# Sheamtic.net
KiCad netlist of a schematic drawn in EAGLE
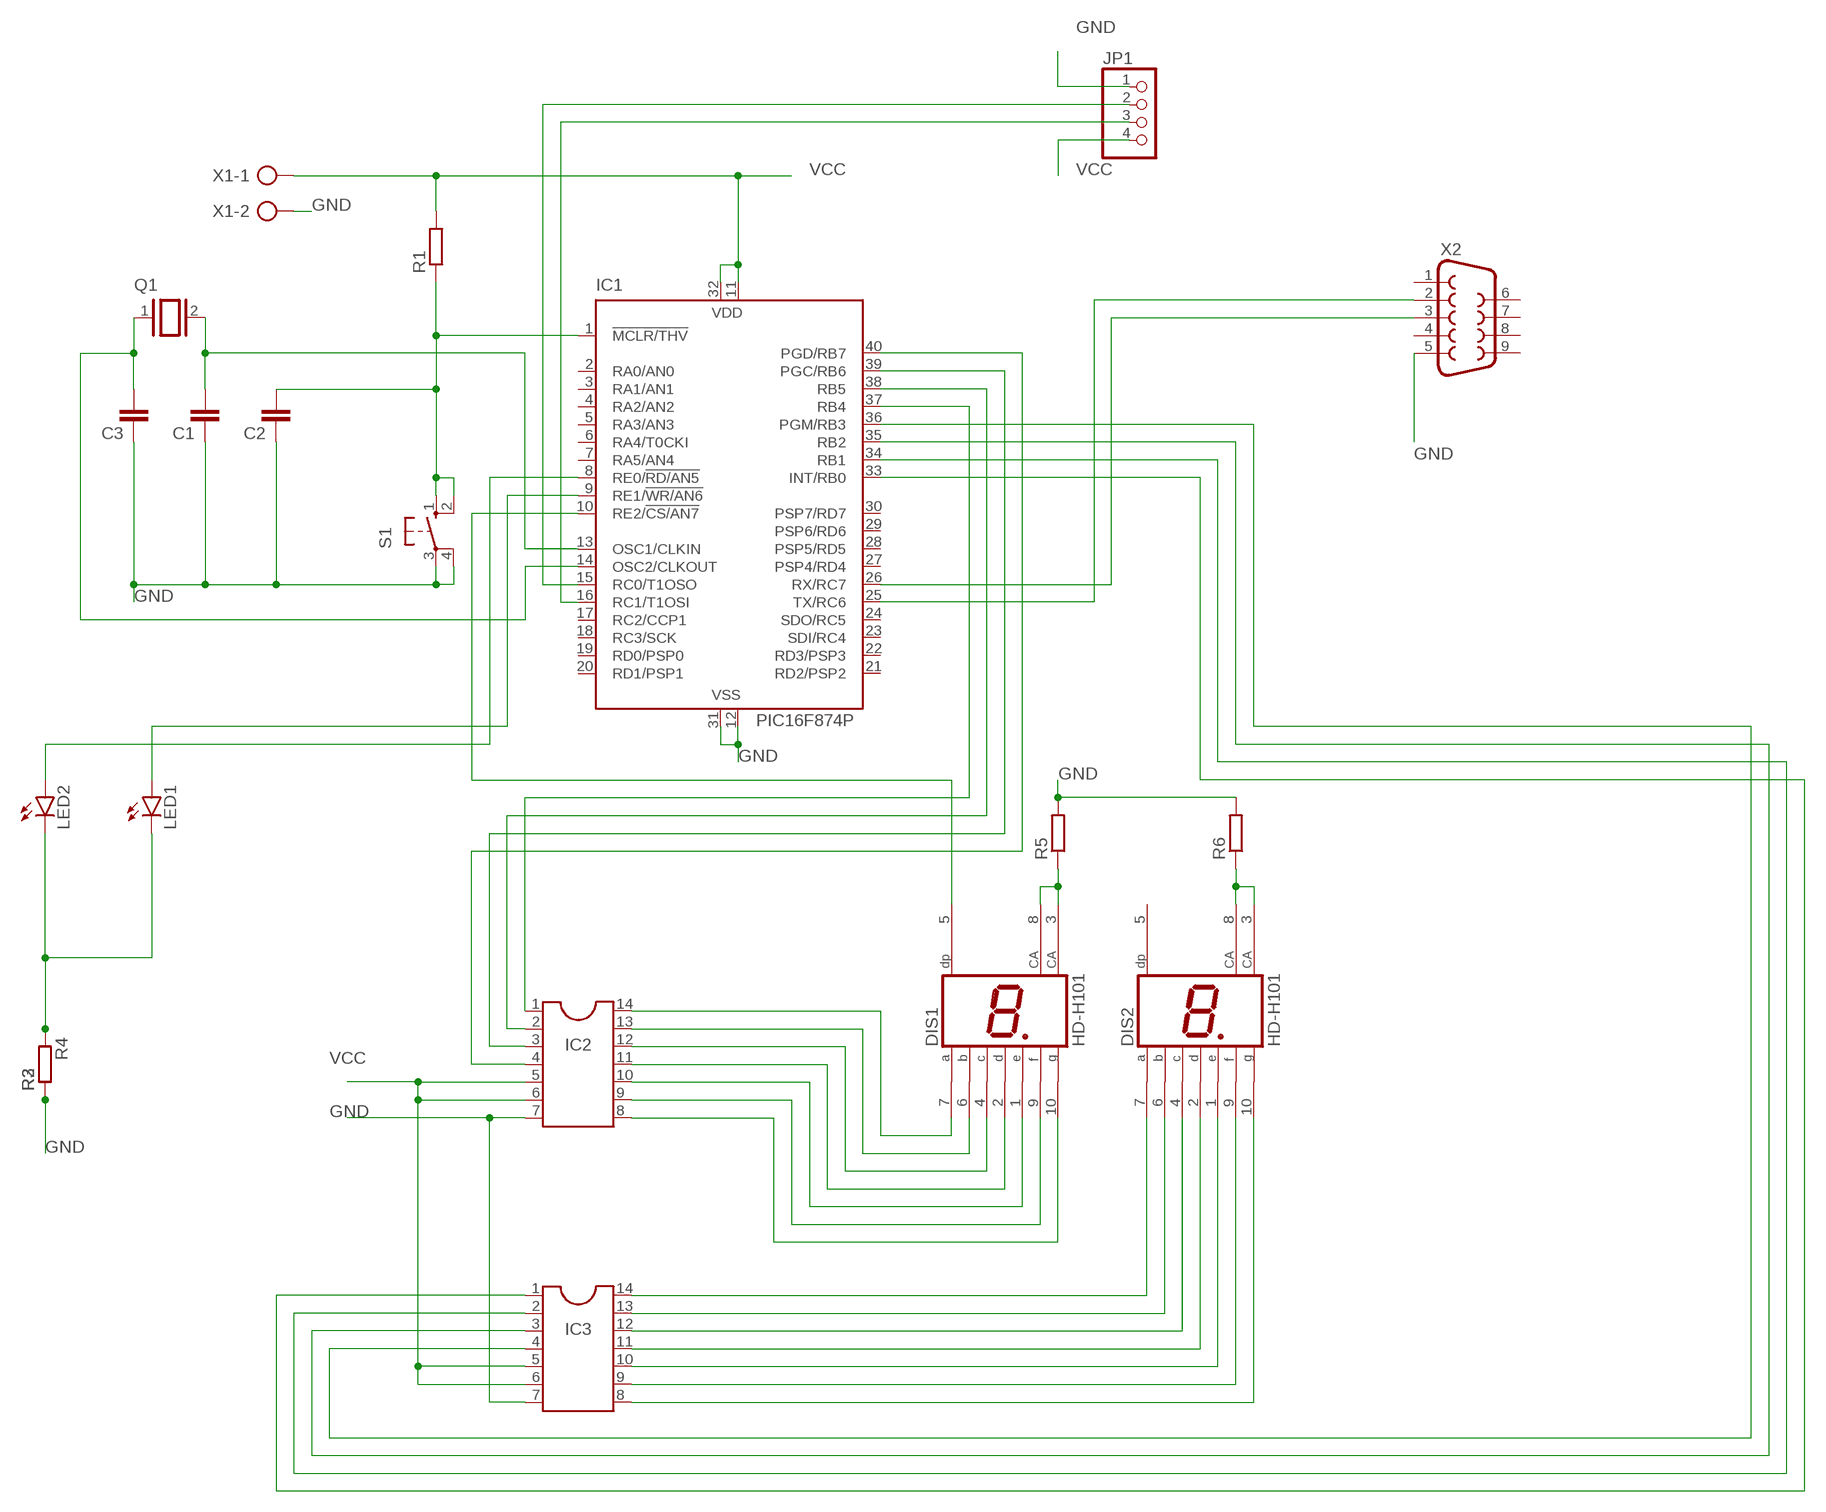
[diagram p0: schematic, sheet 1]

(export (version "E")
  (design (tool "Eeschema 10.0.6"))
  (components
    (comp (ref "C1")
      (value "C-EU025-025X050")
      (footprint "eagle-import:C025-025X050")
      (libsource (lib "eagle-import") (part "C-EU025-025X050"))
    )
    (comp (ref "C2")
      (value "C-EU025-025X050")
      (footprint "eagle-import:C025-025X050")
      (libsource (lib "eagle-import") (part "C-EU025-025X050"))
    )
    (comp (ref "C3")
      (value "C-EU025-025X050")
      (footprint "eagle-import:C025-025X050")
      (libsource (lib "eagle-import") (part "C-EU025-025X050"))
    )
    (comp (ref "DIS1")
      (value "HD-H101")
      (footprint "eagle-import:HDSP-M")
      (libsource (lib "eagle-import") (part "HD-H101"))
    )
    (comp (ref "DIS2")
      (value "HD-H101")
      (footprint "eagle-import:HDSP-M")
      (libsource (lib "eagle-import") (part "HD-H101"))
    )
    (comp (ref "IC1")
      (value "PIC16F874P")
      (footprint "eagle-import:DIL40")
      (fields (field (name "MPN") "PIC16F874-04I/P"))
      (libsource (lib "eagle-import") (part "PIC16F87P4"))
    )
    (comp (ref "IC2")
      (value "DIL14")
      (footprint "eagle-import:DIL14")
      (libsource (lib "eagle-import") (part "DIL14"))
    )
    (comp (ref "IC3")
      (value "DIL14")
      (footprint "eagle-import:DIL14")
      (libsource (lib "eagle-import") (part "DIL14"))
    )
    (comp (ref "JP1")
      (value "PINHD-1X4")
      (footprint "eagle-import:1X04")
      (libsource (lib "eagle-import") (part "PINHD-1X4"))
    )
    (comp (ref "LED1")
      (value "LED5MM")
      (footprint "eagle-import:LED5MM")
      (libsource (lib "eagle-import") (part "LED5MM"))
    )
    (comp (ref "LED2")
      (value "LED5MM")
      (footprint "eagle-import:LED5MM")
      (libsource (lib "eagle-import") (part "LED5MM"))
    )
    (comp (ref "Q1")
      (value "XTAL/S")
      (footprint "eagle-import:QS")
      (libsource (lib "eagle-import") (part "XTAL/S"))
    )
    (comp (ref "R1")
      (value "R-EU_0204/7")
      (footprint "eagle-import:0204_7")
      (libsource (lib "eagle-import") (part "R-EU_0204/7"))
    )
    (comp (ref "R2")
      (value "R-EU_0204/7")
      (footprint "eagle-import:0204_7")
      (libsource (lib "eagle-import") (part "R-EU_0204/7"))
    )
    (comp (ref "R3")
      (value "R-EU_0204/7")
      (footprint "eagle-import:0204_7")
      (libsource (lib "eagle-import") (part "R-EU_0204/7"))
    )
    (comp (ref "R4")
      (value "R-EU_0204/7")
      (footprint "eagle-import:0204_7")
      (libsource (lib "eagle-import") (part "R-EU_0204/7"))
    )
    (comp (ref "R5")
      (value "R-EU_0204/7")
      (footprint "eagle-import:0204_7")
      (libsource (lib "eagle-import") (part "R-EU_0204/7"))
    )
    (comp (ref "R6")
      (value "R-EU_0204/7")
      (footprint "eagle-import:0204_7")
      (libsource (lib "eagle-import") (part "R-EU_0204/7"))
    )
    (comp (ref "S1")
      (value "10-XX")
      (footprint "eagle-import:B3F-10XX")
      (fields (field (name "MPN") "B3F-1000"))
      (libsource (lib "eagle-import") (part "10-XX"))
    )
    (comp (ref "X1")
      (value "AK300/2")
      (footprint "eagle-import:AK300_2")
      (libsource (lib "eagle-import") (part "AK300/2"))
    )
    (comp (ref "X2")
      (value "F09HP")
      (footprint "eagle-import:F09HP")
      (libsource (lib "eagle-import") (part "F09HP"))
    )
  )
  (nets
    (net (code "1") (name "/GND") (class "Default")
      (node (ref "C1") (pin "1") (pinfunction "1_1") (pintype "passive"))
      (node (ref "C2") (pin "1") (pinfunction "1_1") (pintype "passive"))
      (node (ref "C3") (pin "1") (pinfunction "1_1") (pintype "passive"))
      (node (ref "DIS1") (pin "3") (pinfunction "CA_3") (pintype "passive"))
      (node (ref "DIS1") (pin "8") (pinfunction "CA_8") (pintype "passive"))
      (node (ref "IC1") (pin "12") (pinfunction "VSS_12") (pintype "power_in"))
      (node (ref "IC1") (pin "31") (pinfunction "VSS_31") (pintype "power_in"))
      (node (ref "IC2") (pin "7") (pinfunction "7_7") (pintype "passive"))
      (node (ref "IC3") (pin "7") (pinfunction "7_7") (pintype "passive"))
      (node (ref "JP1") (pin "1") (pinfunction "1_1") (pintype "passive"))
      (node (ref "R2") (pin "1") (pinfunction "1_1") (pintype "passive"))
      (node (ref "R3") (pin "1") (pinfunction "1_1") (pintype "passive"))
      (node (ref "R4") (pin "2") (pinfunction "2_2") (pintype "passive"))
      (node (ref "R5") (pin "1") (pinfunction "1_1") (pintype "passive"))
      (node (ref "R5") (pin "2") (pinfunction "2_2") (pintype "passive"))
      (node (ref "R6") (pin "2") (pinfunction "2_2") (pintype "passive"))
      (node (ref "S1") (pin "3") (pinfunction "P_3") (pintype "passive"))
      (node (ref "S1") (pin "4") (pinfunction "P1_4") (pintype "passive"))
      (node (ref "X1") (pin "2") (pinfunction "KL_2") (pintype "passive"))
      (node (ref "X2") (pin "5") (pinfunction "5_5") (pintype "passive"))
    )
    (net (code "2") (name "/VCC") (class "Default")
      (node (ref "IC1") (pin "11") (pinfunction "VDD_11") (pintype "power_in"))
      (node (ref "IC1") (pin "32") (pinfunction "VDD_32") (pintype "power_in"))
      (node (ref "IC2") (pin "5") (pinfunction "5_5") (pintype "passive"))
      (node (ref "IC2") (pin "6") (pinfunction "6_6") (pintype "passive"))
      (node (ref "IC3") (pin "5") (pinfunction "5_5") (pintype "passive"))
      (node (ref "IC3") (pin "6") (pinfunction "6_6") (pintype "passive"))
      (node (ref "JP1") (pin "4") (pinfunction "4_4") (pintype "passive"))
      (node (ref "R1") (pin "2") (pinfunction "2_2") (pintype "passive"))
      (node (ref "X1") (pin "1") (pinfunction "KL_1") (pintype "passive"))
    )
    (net (code "3") (name "Net-(DIS1-A)") (class "Default")
      (node (ref "DIS1") (pin "7") (pinfunction "A_7") (pintype "passive"))
      (node (ref "IC2") (pin "14") (pinfunction "14_14") (pintype "passive"))
    )
    (net (code "4") (name "Net-(DIS1-B)") (class "Default")
      (node (ref "DIS1") (pin "6") (pinfunction "B_6") (pintype "passive"))
      (node (ref "IC2") (pin "13") (pinfunction "13_13") (pintype "passive"))
    )
    (net (code "5") (name "Net-(DIS1-C)") (class "Default")
      (node (ref "DIS1") (pin "4") (pinfunction "C_4") (pintype "passive"))
      (node (ref "IC2") (pin "12") (pinfunction "12_12") (pintype "passive"))
    )
    (net (code "6") (name "Net-(DIS1-D)") (class "Default")
      (node (ref "DIS1") (pin "2") (pinfunction "D_2") (pintype "passive"))
      (node (ref "IC2") (pin "11") (pinfunction "11_11") (pintype "passive"))
    )
    (net (code "7") (name "Net-(DIS1-DP)") (class "Default")
      (node (ref "DIS1") (pin "5") (pinfunction "DP_5") (pintype "passive"))
      (node (ref "IC1") (pin "10") (pinfunction "RE2/~{CS/AN7}_10") (pintype "bidirectional"))
    )
    (net (code "8") (name "Net-(DIS1-E)") (class "Default")
      (node (ref "DIS1") (pin "1") (pinfunction "E_1") (pintype "passive"))
      (node (ref "IC2") (pin "10") (pinfunction "10_10") (pintype "passive"))
    )
    (net (code "9") (name "Net-(DIS1-F)") (class "Default")
      (node (ref "DIS1") (pin "9") (pinfunction "F_9") (pintype "passive"))
      (node (ref "IC2") (pin "9") (pinfunction "9_9") (pintype "passive"))
    )
    (net (code "10") (name "Net-(DIS1-G)") (class "Default")
      (node (ref "DIS1") (pin "10") (pinfunction "G_10") (pintype "passive"))
      (node (ref "IC2") (pin "8") (pinfunction "8_8") (pintype "passive"))
    )
    (net (code "11") (name "Net-(DIS2-A)") (class "Default")
      (node (ref "DIS2") (pin "7") (pinfunction "A_7") (pintype "passive"))
      (node (ref "IC3") (pin "14") (pinfunction "14_14") (pintype "passive"))
    )
    (net (code "12") (name "Net-(DIS2-B)") (class "Default")
      (node (ref "DIS2") (pin "6") (pinfunction "B_6") (pintype "passive"))
      (node (ref "IC3") (pin "13") (pinfunction "13_13") (pintype "passive"))
    )
    (net (code "13") (name "Net-(DIS2-C)") (class "Default")
      (node (ref "DIS2") (pin "4") (pinfunction "C_4") (pintype "passive"))
      (node (ref "IC3") (pin "12") (pinfunction "12_12") (pintype "passive"))
    )
    (net (code "14") (name "Net-(DIS2-CA-Pad3)") (class "Default")
      (node (ref "DIS2") (pin "3") (pinfunction "CA_3") (pintype "passive"))
      (node (ref "DIS2") (pin "8") (pinfunction "CA_8") (pintype "passive"))
      (node (ref "R6") (pin "1") (pinfunction "1_1") (pintype "passive"))
    )
    (net (code "15") (name "Net-(DIS2-D)") (class "Default")
      (node (ref "DIS2") (pin "2") (pinfunction "D_2") (pintype "passive"))
      (node (ref "IC3") (pin "11") (pinfunction "11_11") (pintype "passive"))
    )
    (net (code "16") (name "Net-(DIS2-E)") (class "Default")
      (node (ref "DIS2") (pin "1") (pinfunction "E_1") (pintype "passive"))
      (node (ref "IC3") (pin "10") (pinfunction "10_10") (pintype "passive"))
    )
    (net (code "17") (name "Net-(DIS2-F)") (class "Default")
      (node (ref "DIS2") (pin "9") (pinfunction "F_9") (pintype "passive"))
      (node (ref "IC3") (pin "9") (pinfunction "9_9") (pintype "passive"))
    )
    (net (code "18") (name "Net-(DIS2-G)") (class "Default")
      (node (ref "DIS2") (pin "10") (pinfunction "G_10") (pintype "passive"))
      (node (ref "IC3") (pin "8") (pinfunction "8_8") (pintype "passive"))
    )
    (net (code "19") (name "Net-(IC1-INT{slash}RB0)") (class "Default")
      (node (ref "IC1") (pin "33") (pinfunction "INT/RB0_33") (pintype "bidirectional"))
      (node (ref "IC3") (pin "1") (pinfunction "1_1") (pintype "passive"))
    )
    (net (code "20") (name "Net-(IC1-OSC1{slash}CLKIN)") (class "Default")
      (node (ref "C1") (pin "2") (pinfunction "2_2") (pintype "passive"))
      (node (ref "IC1") (pin "13") (pinfunction "OSC1/CLKIN_13") (pintype "input"))
      (node (ref "Q1") (pin "2") (pinfunction "2_2") (pintype "passive"))
    )
    (net (code "21") (name "Net-(IC1-OSC2{slash}CLKOUT)") (class "Default")
      (node (ref "C3") (pin "2") (pinfunction "2_2") (pintype "passive"))
      (node (ref "IC1") (pin "14") (pinfunction "OSC2/CLKOUT_14") (pintype "output"))
      (node (ref "Q1") (pin "1") (pinfunction "1_1") (pintype "passive"))
    )
    (net (code "22") (name "Net-(IC1-PGC{slash}RB6)") (class "Default")
      (node (ref "IC1") (pin "39") (pinfunction "PGC/RB6_39") (pintype "bidirectional"))
      (node (ref "IC2") (pin "3") (pinfunction "3_3") (pintype "passive"))
    )
    (net (code "23") (name "Net-(IC1-PGD{slash}RB7)") (class "Default")
      (node (ref "IC1") (pin "40") (pinfunction "PGD/RB7_40") (pintype "bidirectional"))
      (node (ref "IC2") (pin "4") (pinfunction "4_4") (pintype "passive"))
    )
    (net (code "24") (name "Net-(IC1-PGM{slash}RB3)") (class "Default")
      (node (ref "IC1") (pin "36") (pinfunction "PGM/RB3_36") (pintype "bidirectional"))
      (node (ref "IC3") (pin "4") (pinfunction "4_4") (pintype "passive"))
    )
    (net (code "25") (name "Net-(IC1-RB1)") (class "Default")
      (node (ref "IC1") (pin "34") (pinfunction "RB1_34") (pintype "bidirectional"))
      (node (ref "IC3") (pin "2") (pinfunction "2_2") (pintype "passive"))
    )
    (net (code "26") (name "Net-(IC1-RB2)") (class "Default")
      (node (ref "IC1") (pin "35") (pinfunction "RB2_35") (pintype "bidirectional"))
      (node (ref "IC3") (pin "3") (pinfunction "3_3") (pintype "passive"))
    )
    (net (code "27") (name "Net-(IC1-RB4)") (class "Default")
      (node (ref "IC1") (pin "37") (pinfunction "RB4_37") (pintype "bidirectional"))
      (node (ref "IC2") (pin "1") (pinfunction "1_1") (pintype "passive"))
    )
    (net (code "28") (name "Net-(IC1-RB5)") (class "Default")
      (node (ref "IC1") (pin "38") (pinfunction "RB5_38") (pintype "bidirectional"))
      (node (ref "IC2") (pin "2") (pinfunction "2_2") (pintype "passive"))
    )
    (net (code "29") (name "Net-(IC1-RC0{slash}T1OSO)") (class "Default")
      (node (ref "IC1") (pin "15") (pinfunction "RC0/T1OSO_15") (pintype "bidirectional"))
      (node (ref "JP1") (pin "2") (pinfunction "2_2") (pintype "passive"))
    )
    (net (code "30") (name "Net-(IC1-RC1{slash}T1OSI)") (class "Default")
      (node (ref "IC1") (pin "16") (pinfunction "RC1/T1OSI_16") (pintype "bidirectional"))
      (node (ref "JP1") (pin "3") (pinfunction "3_3") (pintype "passive"))
    )
    (net (code "31") (name "Net-(IC1-RE0{slash}~{RD{slash}AN5})") (class "Default")
      (node (ref "IC1") (pin "8") (pinfunction "RE0/~{RD/AN5}_8") (pintype "bidirectional"))
      (node (ref "LED2") (pin "A") (pinfunction "A_A") (pintype "passive"))
    )
    (net (code "32") (name "Net-(IC1-RE1{slash}~{WR{slash}AN6})") (class "Default")
      (node (ref "IC1") (pin "9") (pinfunction "RE1/~{WR/AN6}_9") (pintype "bidirectional"))
      (node (ref "LED1") (pin "A") (pinfunction "A_A") (pintype "passive"))
    )
    (net (code "33") (name "Net-(IC1-RX{slash}RC7)") (class "Default")
      (node (ref "IC1") (pin "26") (pinfunction "RX/RC7_26") (pintype "bidirectional"))
      (node (ref "X2") (pin "3") (pinfunction "3_3") (pintype "passive"))
    )
    (net (code "34") (name "Net-(IC1-TX{slash}RC6)") (class "Default")
      (node (ref "IC1") (pin "25") (pinfunction "TX/RC6_25") (pintype "bidirectional"))
      (node (ref "X2") (pin "2") (pinfunction "2_2") (pintype "passive"))
    )
    (net (code "35") (name "Net-(IC1-~{MCLR{slash}THV})") (class "Default")
      (node (ref "C2") (pin "2") (pinfunction "2_2") (pintype "passive"))
      (node (ref "IC1") (pin "1") (pinfunction "~{MCLR/THV}_1") (pintype "input"))
      (node (ref "R1") (pin "1") (pinfunction "1_1") (pintype "passive"))
      (node (ref "S1") (pin "1") (pinfunction "S_1") (pintype "passive"))
      (node (ref "S1") (pin "2") (pinfunction "S1_2") (pintype "passive"))
    )
    (net (code "36") (name "Net-(LED1-C)") (class "Default")
      (node (ref "LED1") (pin "K") (pinfunction "C_K") (pintype "passive"))
      (node (ref "LED2") (pin "K") (pinfunction "C_K") (pintype "passive"))
      (node (ref "R2") (pin "2") (pinfunction "2_2") (pintype "passive"))
      (node (ref "R3") (pin "2") (pinfunction "2_2") (pintype "passive"))
      (node (ref "R4") (pin "1") (pinfunction "1_1") (pintype "passive"))
    )
    (net (code "37") (name "unconnected-(DIS2-DP-Pad5)") (class "Default")
      (node (ref "DIS2") (pin "5") (pinfunction "DP_5") (pintype "passive"))
    )
    (net (code "38") (name "unconnected-(IC1-PSP4{slash}RD4-Pad27)") (class "Default")
      (node (ref "IC1") (pin "27") (pinfunction "PSP4/RD4_27") (pintype "bidirectional"))
    )
    (net (code "39") (name "unconnected-(IC1-PSP5{slash}RD5-Pad28)") (class "Default")
      (node (ref "IC1") (pin "28") (pinfunction "PSP5/RD5_28") (pintype "bidirectional"))
    )
    (net (code "40") (name "unconnected-(IC1-PSP6{slash}RD6-Pad29)") (class "Default")
      (node (ref "IC1") (pin "29") (pinfunction "PSP6/RD6_29") (pintype "bidirectional"))
    )
    (net (code "41") (name "unconnected-(IC1-PSP7{slash}RD7-Pad30)") (class "Default")
      (node (ref "IC1") (pin "30") (pinfunction "PSP7/RD7_30") (pintype "bidirectional"))
    )
    (net (code "42") (name "unconnected-(IC1-RA0{slash}AN0-Pad2)") (class "Default")
      (node (ref "IC1") (pin "2") (pinfunction "RA0/AN0_2") (pintype "bidirectional"))
    )
    (net (code "43") (name "unconnected-(IC1-RA1{slash}AN1-Pad3)") (class "Default")
      (node (ref "IC1") (pin "3") (pinfunction "RA1/AN1_3") (pintype "bidirectional"))
    )
    (net (code "44") (name "unconnected-(IC1-RA2{slash}AN2-Pad4)") (class "Default")
      (node (ref "IC1") (pin "4") (pinfunction "RA2/AN2_4") (pintype "bidirectional"))
    )
    (net (code "45") (name "unconnected-(IC1-RA3{slash}AN3-Pad5)") (class "Default")
      (node (ref "IC1") (pin "5") (pinfunction "RA3/AN3_5") (pintype "bidirectional"))
    )
    (net (code "46") (name "unconnected-(IC1-RA4{slash}T0CKI-Pad6)") (class "Default")
      (node (ref "IC1") (pin "6") (pinfunction "RA4/T0CKI_6") (pintype "bidirectional"))
    )
    (net (code "47") (name "unconnected-(IC1-RA5{slash}AN4-Pad7)") (class "Default")
      (node (ref "IC1") (pin "7") (pinfunction "RA5/AN4_7") (pintype "bidirectional"))
    )
    (net (code "48") (name "unconnected-(IC1-RC2{slash}CCP1-Pad17)") (class "Default")
      (node (ref "IC1") (pin "17") (pinfunction "RC2/CCP1_17") (pintype "bidirectional"))
    )
    (net (code "49") (name "unconnected-(IC1-RC3{slash}SCK-Pad18)") (class "Default")
      (node (ref "IC1") (pin "18") (pinfunction "RC3/SCK_18") (pintype "bidirectional"))
    )
    (net (code "50") (name "unconnected-(IC1-RD0{slash}PSP0-Pad19)") (class "Default")
      (node (ref "IC1") (pin "19") (pinfunction "RD0/PSP0_19") (pintype "bidirectional"))
    )
    (net (code "51") (name "unconnected-(IC1-RD1{slash}PSP1-Pad20)") (class "Default")
      (node (ref "IC1") (pin "20") (pinfunction "RD1/PSP1_20") (pintype "bidirectional"))
    )
    (net (code "52") (name "unconnected-(IC1-RD2{slash}PSP2-Pad21)") (class "Default")
      (node (ref "IC1") (pin "21") (pinfunction "RD2/PSP2_21") (pintype "bidirectional"))
    )
    (net (code "53") (name "unconnected-(IC1-RD3{slash}PSP3-Pad22)") (class "Default")
      (node (ref "IC1") (pin "22") (pinfunction "RD3/PSP3_22") (pintype "bidirectional"))
    )
    (net (code "54") (name "unconnected-(IC1-SDI{slash}RC4-Pad23)") (class "Default")
      (node (ref "IC1") (pin "23") (pinfunction "SDI/RC4_23") (pintype "bidirectional"))
    )
    (net (code "55") (name "unconnected-(IC1-SDO{slash}RC5-Pad24)") (class "Default")
      (node (ref "IC1") (pin "24") (pinfunction "SDO/RC5_24") (pintype "bidirectional"))
    )
    (net (code "56") (name "unconnected-(X2-Pad1)") (class "Default")
      (node (ref "X2") (pin "1") (pinfunction "1_1") (pintype "passive"))
    )
    (net (code "57") (name "unconnected-(X2-Pad4)") (class "Default")
      (node (ref "X2") (pin "4") (pinfunction "4_4") (pintype "passive"))
    )
    (net (code "58") (name "unconnected-(X2-Pad6)") (class "Default")
      (node (ref "X2") (pin "6") (pinfunction "6_6") (pintype "passive"))
    )
    (net (code "59") (name "unconnected-(X2-Pad7)") (class "Default")
      (node (ref "X2") (pin "7") (pinfunction "7_7") (pintype "passive"))
    )
    (net (code "60") (name "unconnected-(X2-Pad8)") (class "Default")
      (node (ref "X2") (pin "8") (pinfunction "8_8") (pintype "passive"))
    )
    (net (code "61") (name "unconnected-(X2-Pad9)") (class "Default")
      (node (ref "X2") (pin "9") (pinfunction "9_9") (pintype "passive"))
    )
  )
)
